# Server_UART_JTAG.net
KiCad netlist of a schematic drawn in Altium Designer
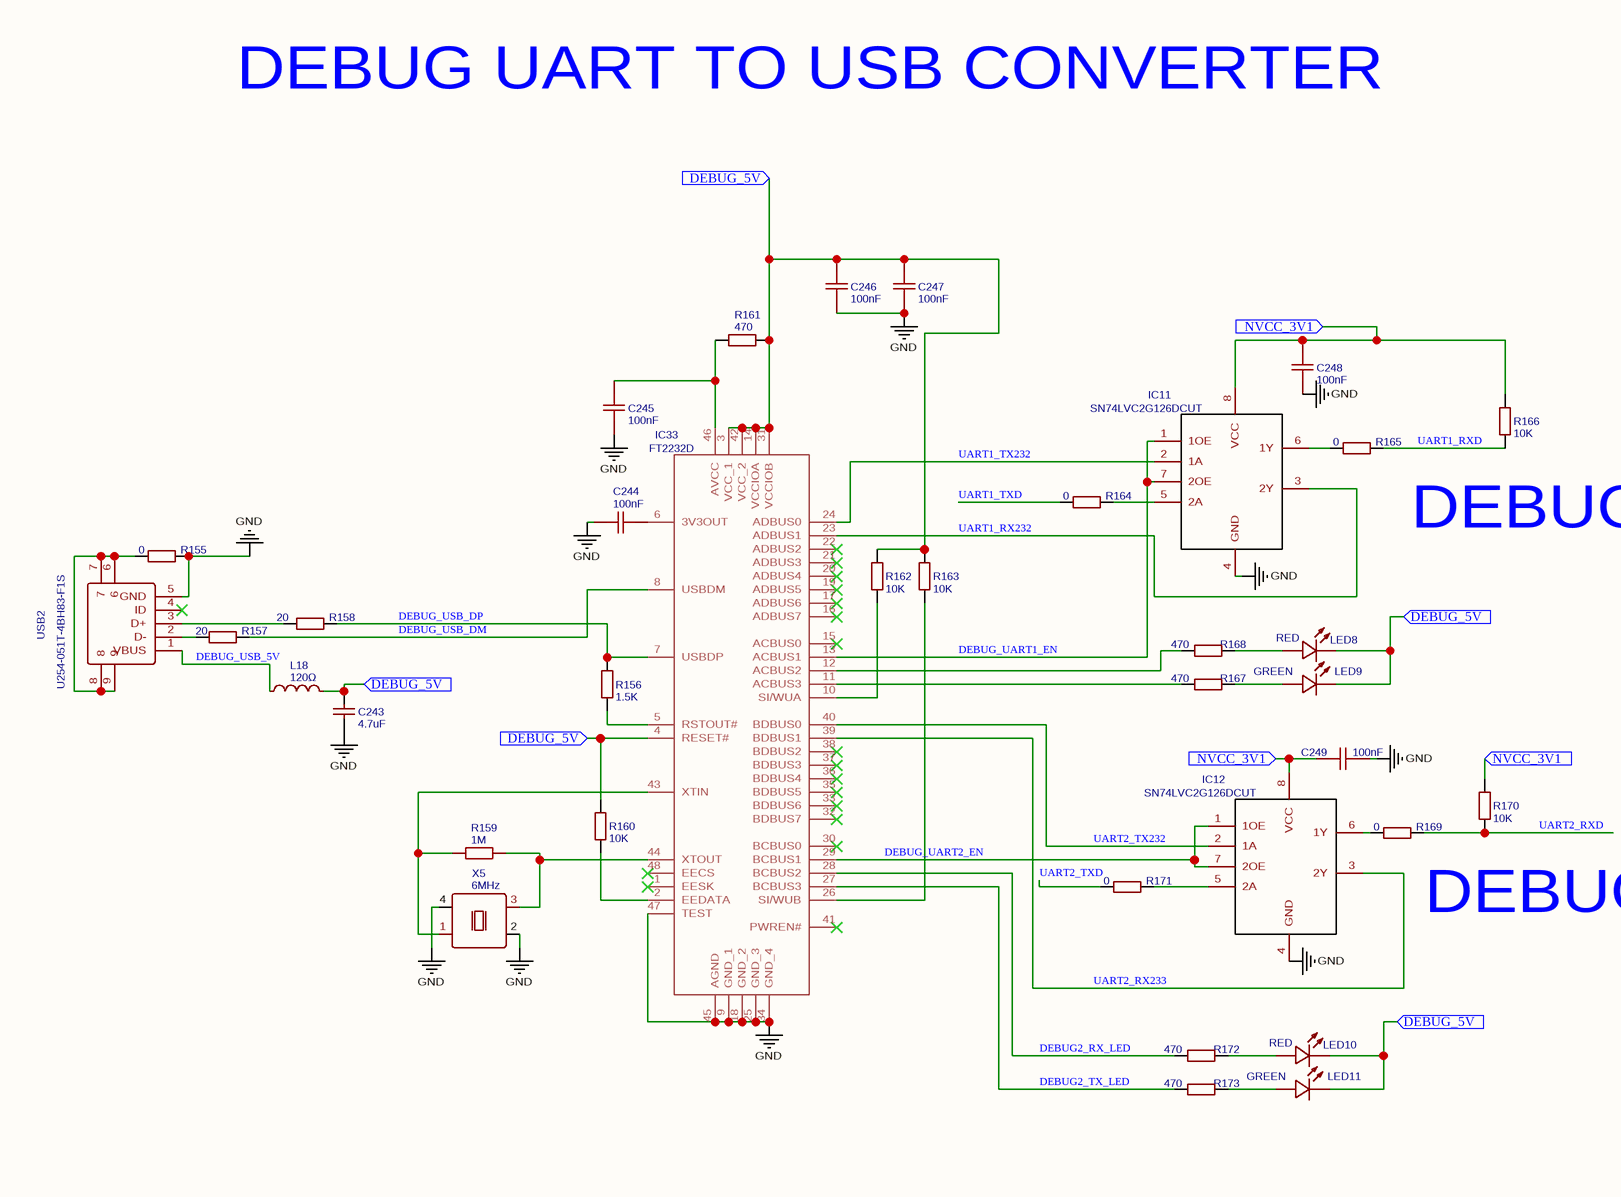
[diagram p0: Server UART & JTAG.schdoc, left]
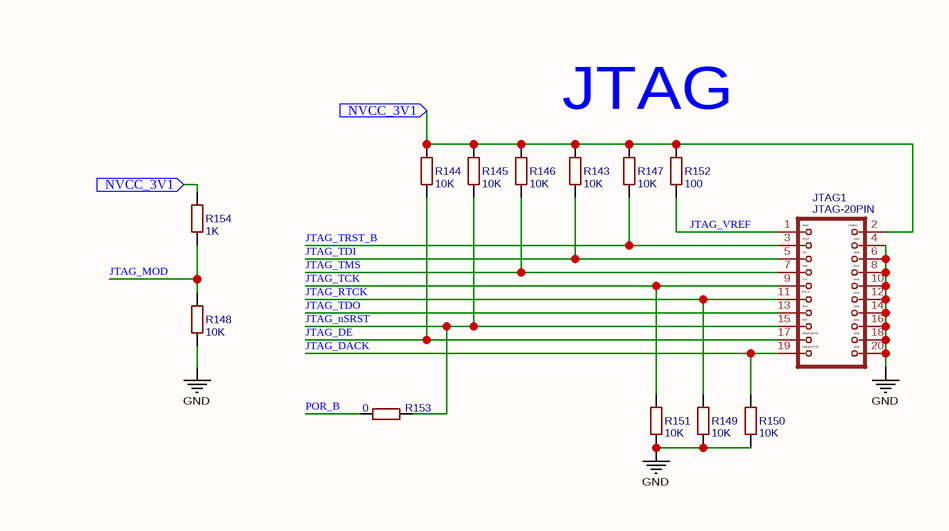
[diagram p1: Server UART & JTAG.schdoc, right]

(export (version "E")
  (design (tool "Eeschema 10.0.6"))
  (components
    (comp (ref "C243")
      (value "4.7uF")
      (fields
        (field (name "BOM_MANUFACTURER PART") "CL10A475KO8NNNC")
        (field (name "BOM_SUPPLIER PART") "C19666")
      )
      (libsource (lib "altium-import") (part "root_1_4.7uF_"))
    )
    (comp (ref "C244")
      (value "100nF")
      (fields
        (field (name "BOM_MANUFACTURER PART") "CC0603KRX7R9BB104")
        (field (name "BOM_SUPPLIER PART") "C14663")
      )
      (libsource (lib "altium-import") (part "root_2_100nF_"))
    )
    (comp (ref "C245")
      (value "100nF")
      (fields
        (field (name "BOM_MANUFACTURER PART") "CC0603KRX7R9BB104")
        (field (name "BOM_SUPPLIER PART") "C14663")
      )
      (libsource (lib "altium-import") (part "root_3_100nF_"))
    )
    (comp (ref "C246")
      (value "100nF")
      (fields
        (field (name "BOM_MANUFACTURER PART") "CC0603KRX7R9BB104")
        (field (name "BOM_SUPPLIER PART") "C14663")
      )
      (libsource (lib "altium-import") (part "root_3_100nF_"))
    )
    (comp (ref "C247")
      (value "100nF")
      (fields
        (field (name "BOM_MANUFACTURER PART") "CC0603KRX7R9BB104")
        (field (name "BOM_SUPPLIER PART") "C14663")
      )
      (libsource (lib "altium-import") (part "root_3_100nF_"))
    )
    (comp (ref "C248")
      (value "100nF")
      (fields
        (field (name "BOM_MANUFACTURER PART") "CC0603KRX7R9BB104")
        (field (name "BOM_SUPPLIER PART") "C14663")
      )
      (libsource (lib "altium-import") (part "root_3_100nF_"))
    )
    (comp (ref "C249")
      (value "100nF")
      (fields
        (field (name "BOM_MANUFACTURER PART") "CC0603KRX7R9BB104")
        (field (name "BOM_SUPPLIER PART") "C14663")
      )
      (libsource (lib "altium-import") (part "root_0_100nF_"))
    )
    (comp (ref "IC11")
      (value "SN74LVC2G126DCUT")
      (fields (field (name "CONTRIBUTOR") "Ke'Ondrae_Mell"))
      (libsource (lib "altium-import") (part "root_0_SN74LVC2G126DCUT_"))
    )
    (comp (ref "IC12")
      (value "SN74LVC2G126DCUT")
      (fields (field (name "CONTRIBUTOR") "Ke'Ondrae_Mell"))
      (libsource (lib "altium-import") (part "root_0_SN74LVC2G126DCUT_"))
    )
    (comp (ref "IC33")
      (value "FT2232D")
      (fields (field (name "CONTRIBUTOR") "Ke'Ondrae_Mell"))
      (libsource (lib "altium-import") (part "root_0_FT2232D_"))
    )
    (comp (ref "JTAG1")
      (value "JTAG-20PIN")
      (description "JTAG 20 Pin Programming Connector")
      (fields (field (name "CONTRIBUTOR") "PatternAgents"))
      (libsource (lib "altium-import") (part "root_0_JTAG-20PIN_"))
    )
    (comp (ref "L18")
      (value "120Ω")
      (fields
        (field (name "BOM_MANUFACTURER PART") "MMZ1005F121ET000")
        (field (name "BOM_SUPPLIER PART") "C89458")
      )
      (libsource (lib "altium-import") (part "root_0_120Ω_"))
    )
    (comp (ref "LED8")
      (value "RED")
      (fields
        (field (name "BOM_MANUFACTURER PART") "16-213UYOC/S530-A2/TR8")
        (field (name "BOM_SUPPLIER PART") "C88330")
      )
      (libsource (lib "altium-import") (part "root_0_RED_"))
    )
    (comp (ref "LED9")
      (value "GREEN")
      (fields
        (field (name "BOM_MANUFACTURER PART") "16-213UYOC/S530-A2/TR8")
        (field (name "BOM_SUPPLIER PART") "C88330")
      )
      (libsource (lib "altium-import") (part "root_0_GREEN_"))
    )
    (comp (ref "LED10")
      (value "RED")
      (fields
        (field (name "BOM_MANUFACTURER PART") "16-213UYOC/S530-A2/TR8")
        (field (name "BOM_SUPPLIER PART") "C88330")
      )
      (libsource (lib "altium-import") (part "root_0_RED_"))
    )
    (comp (ref "LED11")
      (value "GREEN")
      (fields
        (field (name "BOM_MANUFACTURER PART") "16-213UYOC/S530-A2/TR8")
        (field (name "BOM_SUPPLIER PART") "C88330")
      )
      (libsource (lib "altium-import") (part "root_0_GREEN_"))
    )
    (comp (ref "R143")
      (value "10K")
      (fields
        (field (name "BOM_MANUFACTURER PART") "0402WGF1002TCE")
        (field (name "BOM_SUPPLIER PART") "C25744")
      )
      (libsource (lib "altium-import") (part "root_1_10K_"))
    )
    (comp (ref "R144")
      (value "10K")
      (fields
        (field (name "BOM_MANUFACTURER PART") "0402WGF1002TCE")
        (field (name "BOM_SUPPLIER PART") "C25744")
      )
      (libsource (lib "altium-import") (part "root_1_10K_"))
    )
    (comp (ref "R145")
      (value "10K")
      (fields
        (field (name "BOM_MANUFACTURER PART") "0402WGF1002TCE")
        (field (name "BOM_SUPPLIER PART") "C25744")
      )
      (libsource (lib "altium-import") (part "root_1_10K_"))
    )
    (comp (ref "R146")
      (value "10K")
      (fields
        (field (name "BOM_MANUFACTURER PART") "0402WGF1002TCE")
        (field (name "BOM_SUPPLIER PART") "C25744")
      )
      (libsource (lib "altium-import") (part "root_1_10K_"))
    )
    (comp (ref "R147")
      (value "10K")
      (fields
        (field (name "BOM_MANUFACTURER PART") "0402WGF1002TCE")
        (field (name "BOM_SUPPLIER PART") "C25744")
      )
      (libsource (lib "altium-import") (part "root_1_10K_"))
    )
    (comp (ref "R148")
      (value "10K")
      (fields
        (field (name "BOM_MANUFACTURER PART") "0402WGF1002TCE")
        (field (name "BOM_SUPPLIER PART") "C25744")
      )
      (libsource (lib "altium-import") (part "root_1_10K_"))
    )
    (comp (ref "R149")
      (value "10K")
      (fields
        (field (name "BOM_MANUFACTURER PART") "0402WGF1002TCE")
        (field (name "BOM_SUPPLIER PART") "C25744")
      )
      (libsource (lib "altium-import") (part "root_1_10K_"))
    )
    (comp (ref "R150")
      (value "10K")
      (fields
        (field (name "BOM_MANUFACTURER PART") "0402WGF1002TCE")
        (field (name "BOM_SUPPLIER PART") "C25744")
      )
      (libsource (lib "altium-import") (part "root_1_10K_"))
    )
    (comp (ref "R151")
      (value "10K")
      (fields
        (field (name "BOM_MANUFACTURER PART") "0402WGF1002TCE")
        (field (name "BOM_SUPPLIER PART") "C25744")
      )
      (libsource (lib "altium-import") (part "root_1_10K_"))
    )
    (comp (ref "R152")
      (value "100")
      (fields
        (field (name "BOM_MANUFACTURER PART") "TC0225F1000TCE")
        (field (name "BOM_SUPPLIER PART") "C98836")
      )
      (libsource (lib "altium-import") (part "root_1_100_"))
    )
    (comp (ref "R153")
      (value "0")
      (fields
        (field (name "BOM_MANUFACTURER PART") "RK73Z1ETTP")
        (field (name "BOM_SUPPLIER PART") "C131359")
      )
      (libsource (lib "altium-import") (part "root_0_0_"))
    )
    (comp (ref "R154")
      (value "1K")
      (fields
        (field (name "BOM_MANUFACTURER PART") "TC0225F1001TCE")
        (field (name "BOM_SUPPLIER PART") "C98841")
      )
      (libsource (lib "altium-import") (part "root_1_1K_"))
    )
    (comp (ref "R155")
      (value "0")
      (fields
        (field (name "BOM_MANUFACTURER PART") "RK73Z1ETTP")
        (field (name "BOM_SUPPLIER PART") "C131359")
      )
      (libsource (lib "altium-import") (part "root_0_0_"))
    )
    (comp (ref "R156")
      (value "1.5K")
      (fields
        (field (name "BOM_MANUFACTURER PART") "0402WGF1501TCE")
        (field (name "BOM_SUPPLIER PART") "C25867")
      )
      (libsource (lib "altium-import") (part "root_1_1.5K_"))
    )
    (comp (ref "R157")
      (value "20")
      (fields
        (field (name "BOM_MANUFACTURER PART") "0805W8F200JT5E")
        (field (name "BOM_SUPPLIER PART") "C17544")
      )
      (libsource (lib "altium-import") (part "root_0_20_"))
    )
    (comp (ref "R158")
      (value "20")
      (fields
        (field (name "BOM_MANUFACTURER PART") "0805W8F200JT5E")
        (field (name "BOM_SUPPLIER PART") "C17544")
      )
      (libsource (lib "altium-import") (part "root_0_20_"))
    )
    (comp (ref "R159")
      (value "1M")
      (fields
        (field (name "BOM_SUPPLIER PART") "C269705")
        (field (name "BOM_MANUFACTURER PART") "RMC06031M1%N")
        (field (name "CONTRIBUTOR") "LCSC")
      )
      (libsource (lib "altium-import") (part "root_0_1M_"))
    )
    (comp (ref "R160")
      (value "10K")
      (fields
        (field (name "BOM_MANUFACTURER PART") "0402WGF1002TCE")
        (field (name "BOM_SUPPLIER PART") "C25744")
      )
      (libsource (lib "altium-import") (part "root_1_10K_"))
    )
    (comp (ref "R161")
      (value "470")
      (fields
        (field (name "BOM_MANUFACTURER PART") "0402WGF4700TCE")
        (field (name "BOM_SUPPLIER PART") "C25117")
      )
      (libsource (lib "altium-import") (part "root_0_470_"))
    )
    (comp (ref "R162")
      (value "10K")
      (fields
        (field (name "BOM_MANUFACTURER PART") "0402WGF1002TCE")
        (field (name "BOM_SUPPLIER PART") "C25744")
      )
      (libsource (lib "altium-import") (part "root_1_10K_"))
    )
    (comp (ref "R163")
      (value "10K")
      (fields
        (field (name "BOM_MANUFACTURER PART") "0402WGF1002TCE")
        (field (name "BOM_SUPPLIER PART") "C25744")
      )
      (libsource (lib "altium-import") (part "root_1_10K_"))
    )
    (comp (ref "R164")
      (value "0")
      (fields
        (field (name "BOM_MANUFACTURER PART") "RK73Z1ETTP")
        (field (name "BOM_SUPPLIER PART") "C131359")
      )
      (libsource (lib "altium-import") (part "root_0_0_"))
    )
    (comp (ref "R165")
      (value "0")
      (fields
        (field (name "BOM_MANUFACTURER PART") "RK73Z1ETTP")
        (field (name "BOM_SUPPLIER PART") "C131359")
      )
      (libsource (lib "altium-import") (part "root_0_0_"))
    )
    (comp (ref "R166")
      (value "10K")
      (fields
        (field (name "BOM_MANUFACTURER PART") "0402WGF1002TCE")
        (field (name "BOM_SUPPLIER PART") "C25744")
      )
      (libsource (lib "altium-import") (part "root_1_10K_"))
    )
    (comp (ref "R167")
      (value "470")
      (fields
        (field (name "BOM_MANUFACTURER PART") "0402WGF4700TCE")
        (field (name "BOM_SUPPLIER PART") "C25117")
      )
      (libsource (lib "altium-import") (part "root_0_470_"))
    )
    (comp (ref "R168")
      (value "470")
      (fields
        (field (name "BOM_MANUFACTURER PART") "0402WGF4700TCE")
        (field (name "BOM_SUPPLIER PART") "C25117")
      )
      (libsource (lib "altium-import") (part "root_0_470_"))
    )
    (comp (ref "R169")
      (value "0")
      (fields
        (field (name "BOM_MANUFACTURER PART") "RK73Z1ETTP")
        (field (name "BOM_SUPPLIER PART") "C131359")
      )
      (libsource (lib "altium-import") (part "root_0_0_"))
    )
    (comp (ref "R170")
      (value "10K")
      (fields
        (field (name "BOM_MANUFACTURER PART") "0402WGF1002TCE")
        (field (name "BOM_SUPPLIER PART") "C25744")
      )
      (libsource (lib "altium-import") (part "root_1_10K_"))
    )
    (comp (ref "R171")
      (value "0")
      (fields
        (field (name "BOM_MANUFACTURER PART") "RK73Z1ETTP")
        (field (name "BOM_SUPPLIER PART") "C131359")
      )
      (libsource (lib "altium-import") (part "root_0_0_"))
    )
    (comp (ref "R172")
      (value "470")
      (fields
        (field (name "BOM_MANUFACTURER PART") "0402WGF4700TCE")
        (field (name "BOM_SUPPLIER PART") "C25117")
      )
      (libsource (lib "altium-import") (part "root_0_470_"))
    )
    (comp (ref "R173")
      (value "470")
      (fields
        (field (name "BOM_MANUFACTURER PART") "0402WGF4700TCE")
        (field (name "BOM_SUPPLIER PART") "C25117")
      )
      (libsource (lib "altium-import") (part "root_0_470_"))
    )
    (comp (ref "USB2")
      (value "U254-051T-4BH83-F1S")
      (fields (field (name "BOM_SUPPLIER PART") "C397452") (field (name "CONTRIBUTOR") "LCSC"))
      (libsource (lib "altium-import") (part "root_2_U254-051T-4BH83-F1S_"))
    )
    (comp (ref "X5")
      (value "6MHz")
      (fields
        (field (name "BOM_SUPPLIER PART") "C295516")
        (field (name "BOM_MANUFACTURER PART") "OVETGLJANF-6MHZ")
        (field (name "CONTRIBUTOR") "LCSC")
      )
      (libsource (lib "altium-import") (part "root_0_6MHz_"))
    )
  )
  (nets
    (net (code "1") (name "/DEBUG2_RX_LED") (class "Default")
      (node (ref "IC33") (pin "28") (pinfunction "BCBUS2_28") (pintype "passive"))
      (node (ref "R172") (pin "1") (pinfunction "1_1") (pintype "passive"))
    )
    (net (code "2") (name "/DEBUG2_TX_LED") (class "Default")
      (node (ref "IC33") (pin "27") (pinfunction "BCBUS3_27") (pintype "passive"))
      (node (ref "R173") (pin "1") (pinfunction "1_1") (pintype "passive"))
    )
    (net (code "3") (name "/DEBUG_5V") (class "Default")
      (node (ref "C243") (pin "2") (pinfunction "2_2") (pintype "passive"))
      (node (ref "C246") (pin "1") (pinfunction "1_1") (pintype "passive"))
      (node (ref "C247") (pin "1") (pinfunction "1_1") (pintype "passive"))
      (node (ref "IC33") (pin "14") (pinfunction "VCCIOA_14") (pintype "passive"))
      (node (ref "IC33") (pin "3") (pinfunction "VCC_1_3") (pintype "passive"))
      (node (ref "IC33") (pin "31") (pinfunction "VCCIOB_31") (pintype "passive"))
      (node (ref "IC33") (pin "4") (pinfunction "RESET#_4") (pintype "passive"))
      (node (ref "IC33") (pin "42") (pinfunction "VCC_2_42") (pintype "passive"))
      (node (ref "L18") (pin "2") (pinfunction "2_2") (pintype "passive"))
      (node (ref "LED10") (pin "2") (pinfunction "K_2") (pintype "passive"))
      (node (ref "LED11") (pin "2") (pinfunction "K_2") (pintype "passive"))
      (node (ref "LED8") (pin "2") (pinfunction "K_2") (pintype "passive"))
      (node (ref "LED9") (pin "2") (pinfunction "K_2") (pintype "passive"))
      (node (ref "R160") (pin "2") (pinfunction "2_2") (pintype "passive"))
      (node (ref "R161") (pin "2") (pinfunction "2_2") (pintype "passive"))
      (node (ref "R162") (pin "2") (pinfunction "2_2") (pintype "passive"))
      (node (ref "R163") (pin "2") (pinfunction "2_2") (pintype "passive"))
    )
    (net (code "4") (name "/DEBUG_UART1_EN") (class "Default")
      (node (ref "IC11") (pin "1") (pinfunction "1OE_1") (pintype "passive"))
      (node (ref "IC11") (pin "7") (pinfunction "2OE_7") (pintype "passive"))
      (node (ref "IC33") (pin "13") (pinfunction "ACBUS1_13") (pintype "passive"))
    )
    (net (code "5") (name "/DEBUG_UART2_EN") (class "Default")
      (node (ref "IC12") (pin "1") (pinfunction "1OE_1") (pintype "passive"))
      (node (ref "IC12") (pin "7") (pinfunction "2OE_7") (pintype "passive"))
      (node (ref "IC33") (pin "29") (pinfunction "BCBUS1_29") (pintype "passive"))
    )
    (net (code "6") (name "/DEBUG_USB_5V") (class "Default")
      (node (ref "L18") (pin "1") (pinfunction "1_1") (pintype "passive"))
      (node (ref "USB2") (pin "1") (pinfunction "VBUS_1") (pintype "passive"))
    )
    (net (code "7") (name "/DEBUG_USB_DM") (class "Default")
      (node (ref "IC33") (pin "8") (pinfunction "USBDM_8") (pintype "passive"))
      (node (ref "R157") (pin "2") (pinfunction "2_2") (pintype "passive"))
    )
    (net (code "8") (name "/DEBUG_USB_DP") (class "Default")
      (node (ref "IC33") (pin "7") (pinfunction "USBDP_7") (pintype "passive"))
      (node (ref "R156") (pin "2") (pinfunction "2_2") (pintype "passive"))
      (node (ref "R158") (pin "2") (pinfunction "2_2") (pintype "passive"))
    )
    (net (code "9") (name "/JTAG_DACK") (class "Default")
      (node (ref "JTAG1") (pin "19") (pinfunction "19_19") (pintype "passive"))
      (node (ref "R150") (pin "2") (pinfunction "2_2") (pintype "passive"))
    )
    (net (code "10") (name "/JTAG_DE") (class "Default")
      (node (ref "JTAG1") (pin "17") (pinfunction "17_17") (pintype "passive"))
      (node (ref "R144") (pin "1") (pinfunction "1_1") (pintype "passive"))
    )
    (net (code "11") (name "/JTAG_MOD") (class "Default")
      (node (ref "R148") (pin "2") (pinfunction "2_2") (pintype "passive"))
      (node (ref "R154") (pin "1") (pinfunction "1_1") (pintype "passive"))
    )
    (net (code "12") (name "/JTAG_RTCK") (class "Default")
      (node (ref "JTAG1") (pin "11") (pinfunction "11_11") (pintype "passive"))
      (node (ref "R149") (pin "2") (pinfunction "2_2") (pintype "passive"))
    )
    (net (code "13") (name "/JTAG_TCK") (class "Default")
      (node (ref "JTAG1") (pin "9") (pinfunction "9_9") (pintype "passive"))
      (node (ref "R151") (pin "2") (pinfunction "2_2") (pintype "passive"))
    )
    (net (code "14") (name "/JTAG_TDI") (class "Default")
      (node (ref "JTAG1") (pin "5") (pinfunction "5_5") (pintype "passive"))
      (node (ref "R143") (pin "1") (pinfunction "1_1") (pintype "passive"))
    )
    (net (code "15") (name "/JTAG_TDO") (class "Default")
      (node (ref "JTAG1") (pin "13") (pinfunction "13_13") (pintype "passive"))
    )
    (net (code "16") (name "/JTAG_TMS") (class "Default")
      (node (ref "JTAG1") (pin "7") (pinfunction "7_7") (pintype "passive"))
      (node (ref "R146") (pin "1") (pinfunction "1_1") (pintype "passive"))
    )
    (net (code "17") (name "/JTAG_TRST_B") (class "Default")
      (node (ref "JTAG1") (pin "3") (pinfunction "3_3") (pintype "passive"))
      (node (ref "R147") (pin "1") (pinfunction "1_1") (pintype "passive"))
    )
    (net (code "18") (name "/JTAG_VREF") (class "Default")
      (node (ref "JTAG1") (pin "1") (pinfunction "1_1") (pintype "passive"))
      (node (ref "R152") (pin "1") (pinfunction "1_1") (pintype "passive"))
    )
    (net (code "19") (name "/JTAG_nSRST") (class "Default")
      (node (ref "JTAG1") (pin "15") (pinfunction "15_15") (pintype "passive"))
      (node (ref "R145") (pin "1") (pinfunction "1_1") (pintype "passive"))
      (node (ref "R153") (pin "2") (pinfunction "2_2") (pintype "passive"))
    )
    (net (code "20") (name "/NVCC_3V1") (class "Default")
      (node (ref "C248") (pin "1") (pinfunction "1_1") (pintype "passive"))
      (node (ref "C249") (pin "1") (pinfunction "1_1") (pintype "passive"))
      (node (ref "IC11") (pin "8") (pinfunction "VCC_8") (pintype "passive"))
      (node (ref "IC12") (pin "8") (pinfunction "VCC_8") (pintype "passive"))
      (node (ref "JTAG1") (pin "2") (pinfunction "2_2") (pintype "passive"))
      (node (ref "R143") (pin "2") (pinfunction "2_2") (pintype "passive"))
      (node (ref "R144") (pin "2") (pinfunction "2_2") (pintype "passive"))
      (node (ref "R145") (pin "2") (pinfunction "2_2") (pintype "passive"))
      (node (ref "R146") (pin "2") (pinfunction "2_2") (pintype "passive"))
      (node (ref "R147") (pin "2") (pinfunction "2_2") (pintype "passive"))
      (node (ref "R152") (pin "2") (pinfunction "2_2") (pintype "passive"))
      (node (ref "R154") (pin "2") (pinfunction "2_2") (pintype "passive"))
      (node (ref "R166") (pin "2") (pinfunction "2_2") (pintype "passive"))
      (node (ref "R170") (pin "2") (pinfunction "2_2") (pintype "passive"))
    )
    (net (code "21") (name "/POR_B") (class "Default")
      (node (ref "R153") (pin "1") (pinfunction "1_1") (pintype "passive"))
    )
    (net (code "22") (name "/UART1_RX232") (class "Default")
      (node (ref "IC11") (pin "3") (pinfunction "2Y_3") (pintype "passive"))
      (node (ref "IC33") (pin "23") (pinfunction "ADBUS1_23") (pintype "passive"))
    )
    (net (code "23") (name "/UART1_RXD") (class "Default")
      (node (ref "R165") (pin "2") (pinfunction "2_2") (pintype "passive"))
      (node (ref "R166") (pin "1") (pinfunction "1_1") (pintype "passive"))
    )
    (net (code "24") (name "/UART1_TX232") (class "Default")
      (node (ref "IC11") (pin "2") (pinfunction "1A_2") (pintype "passive"))
      (node (ref "IC33") (pin "24") (pinfunction "ADBUS0_24") (pintype "passive"))
    )
    (net (code "25") (name "/UART1_TXD") (class "Default")
      (node (ref "R164") (pin "1") (pinfunction "1_1") (pintype "passive"))
    )
    (net (code "26") (name "/UART2_RX233") (class "Default")
      (node (ref "IC12") (pin "3") (pinfunction "2Y_3") (pintype "passive"))
      (node (ref "IC33") (pin "39") (pinfunction "BDBUS1_39") (pintype "passive"))
    )
    (net (code "27") (name "/UART2_RXD") (class "Default")
      (node (ref "R169") (pin "2") (pinfunction "2_2") (pintype "passive"))
      (node (ref "R170") (pin "1") (pinfunction "1_1") (pintype "passive"))
    )
    (net (code "28") (name "/UART2_TX232") (class "Default")
      (node (ref "IC12") (pin "2") (pinfunction "1A_2") (pintype "passive"))
      (node (ref "IC33") (pin "40") (pinfunction "BDBUS0_40") (pintype "passive"))
    )
    (net (code "29") (name "/UART2_TXD") (class "Default")
      (node (ref "R171") (pin "1") (pinfunction "1_1") (pintype "passive"))
    )
    (net (code "30") (name "GND") (class "Default")
      (node (ref "C243") (pin "1") (pinfunction "1_1") (pintype "passive"))
      (node (ref "C244") (pin "2") (pinfunction "2_2") (pintype "passive"))
      (node (ref "C245") (pin "2") (pinfunction "2_2") (pintype "passive"))
      (node (ref "C246") (pin "2") (pinfunction "2_2") (pintype "passive"))
      (node (ref "C247") (pin "2") (pinfunction "2_2") (pintype "passive"))
      (node (ref "C248") (pin "2") (pinfunction "2_2") (pintype "passive"))
      (node (ref "C249") (pin "2") (pinfunction "2_2") (pintype "passive"))
      (node (ref "IC11") (pin "4") (pinfunction "GND_4") (pintype "passive"))
      (node (ref "IC12") (pin "4") (pinfunction "GND_4") (pintype "passive"))
      (node (ref "IC33") (pin "18") (pinfunction "GND_2_18") (pintype "passive"))
      (node (ref "IC33") (pin "25") (pinfunction "GND_3_25") (pintype "passive"))
      (node (ref "IC33") (pin "34") (pinfunction "GND_4_34") (pintype "passive"))
      (node (ref "IC33") (pin "45") (pinfunction "AGND_45") (pintype "passive"))
      (node (ref "IC33") (pin "47") (pinfunction "TEST_47") (pintype "passive"))
      (node (ref "IC33") (pin "9") (pinfunction "GND_1_9") (pintype "passive"))
      (node (ref "JTAG1") (pin "10") (pinfunction "10_10") (pintype "passive"))
      (node (ref "JTAG1") (pin "12") (pinfunction "12_12") (pintype "passive"))
      (node (ref "JTAG1") (pin "14") (pinfunction "14_14") (pintype "passive"))
      (node (ref "JTAG1") (pin "16") (pinfunction "16_16") (pintype "passive"))
      (node (ref "JTAG1") (pin "18") (pinfunction "18_18") (pintype "passive"))
      (node (ref "JTAG1") (pin "20") (pinfunction "20_20") (pintype "passive"))
      (node (ref "JTAG1") (pin "4") (pinfunction "4_4") (pintype "passive"))
      (node (ref "JTAG1") (pin "6") (pinfunction "6_6") (pintype "passive"))
      (node (ref "JTAG1") (pin "8") (pinfunction "8_8") (pintype "passive"))
      (node (ref "R148") (pin "1") (pinfunction "1_1") (pintype "passive"))
      (node (ref "R149") (pin "1") (pinfunction "1_1") (pintype "passive"))
      (node (ref "R150") (pin "1") (pinfunction "1_1") (pintype "passive"))
      (node (ref "R151") (pin "1") (pinfunction "1_1") (pintype "passive"))
      (node (ref "R155") (pin "2") (pinfunction "2_2") (pintype "passive"))
      (node (ref "USB2") (pin "5") (pinfunction "GND_5") (pintype "passive"))
      (node (ref "X5") (pin "2") (pinfunction "GND_2") (pintype "passive"))
      (node (ref "X5") (pin "4") (pinfunction "VCC_4") (pintype "passive"))
    )
    (net (code "31") (name "Net-(IC11-1Y)") (class "Default")
      (node (ref "IC11") (pin "6") (pinfunction "1Y_6") (pintype "passive"))
      (node (ref "R165") (pin "1") (pinfunction "1_1") (pintype "passive"))
    )
    (net (code "32") (name "Net-(IC11-2A)") (class "Default")
      (node (ref "IC11") (pin "5") (pinfunction "2A_5") (pintype "passive"))
      (node (ref "R164") (pin "2") (pinfunction "2_2") (pintype "passive"))
    )
    (net (code "33") (name "Net-(IC12-1Y)") (class "Default")
      (node (ref "IC12") (pin "6") (pinfunction "1Y_6") (pintype "passive"))
      (node (ref "R169") (pin "1") (pinfunction "1_1") (pintype "passive"))
    )
    (net (code "34") (name "Net-(IC12-2A)") (class "Default")
      (node (ref "IC12") (pin "5") (pinfunction "2A_5") (pintype "passive"))
      (node (ref "R171") (pin "2") (pinfunction "2_2") (pintype "passive"))
    )
    (net (code "35") (name "Net-(IC33-3V3OUT)") (class "Default")
      (node (ref "C244") (pin "1") (pinfunction "1_1") (pintype "passive"))
      (node (ref "IC33") (pin "6") (pinfunction "3V3OUT_6") (pintype "passive"))
    )
    (net (code "36") (name "Net-(IC33-ACBUS2)") (class "Default")
      (node (ref "IC33") (pin "12") (pinfunction "ACBUS2_12") (pintype "passive"))
      (node (ref "R168") (pin "1") (pinfunction "1_1") (pintype "passive"))
    )
    (net (code "37") (name "Net-(IC33-ACBUS3)") (class "Default")
      (node (ref "IC33") (pin "11") (pinfunction "ACBUS3_11") (pintype "passive"))
      (node (ref "R167") (pin "1") (pinfunction "1_1") (pintype "passive"))
    )
    (net (code "38") (name "Net-(IC33-AVCC)") (class "Default")
      (node (ref "C245") (pin "1") (pinfunction "1_1") (pintype "passive"))
      (node (ref "IC33") (pin "46") (pinfunction "AVCC_46") (pintype "passive"))
      (node (ref "R161") (pin "1") (pinfunction "1_1") (pintype "passive"))
    )
    (net (code "39") (name "Net-(IC33-EEDATA)") (class "Default")
      (node (ref "IC33") (pin "2") (pinfunction "EEDATA_2") (pintype "passive"))
      (node (ref "R160") (pin "1") (pinfunction "1_1") (pintype "passive"))
    )
    (net (code "40") (name "Net-(IC33-RSTOUT#)") (class "Default")
      (node (ref "IC33") (pin "5") (pinfunction "RSTOUT#_5") (pintype "passive"))
      (node (ref "R156") (pin "1") (pinfunction "1_1") (pintype "passive"))
    )
    (net (code "41") (name "Net-(IC33-SI{slash}WUA)") (class "Default")
      (node (ref "IC33") (pin "10") (pinfunction "SI/WUA_10") (pintype "passive"))
      (node (ref "R162") (pin "1") (pinfunction "1_1") (pintype "passive"))
    )
    (net (code "42") (name "Net-(IC33-SI{slash}WUB)") (class "Default")
      (node (ref "IC33") (pin "26") (pinfunction "SI/WUB_26") (pintype "passive"))
      (node (ref "R163") (pin "1") (pinfunction "1_1") (pintype "passive"))
    )
    (net (code "43") (name "Net-(IC33-XTIN)") (class "Default")
      (node (ref "IC33") (pin "43") (pinfunction "XTIN_43") (pintype "passive"))
      (node (ref "R159") (pin "1") (pinfunction "1_1") (pintype "passive"))
      (node (ref "X5") (pin "1") (pinfunction "tri_1") (pintype "passive"))
    )
    (net (code "44") (name "Net-(IC33-XTOUT)") (class "Default")
      (node (ref "IC33") (pin "44") (pinfunction "XTOUT_44") (pintype "passive"))
      (node (ref "R159") (pin "2") (pinfunction "2_2") (pintype "passive"))
      (node (ref "X5") (pin "3") (pinfunction "OUT_3") (pintype "passive"))
    )
    (net (code "45") (name "Net-(LED8-A)") (class "Default")
      (node (ref "LED8") (pin "1") (pinfunction "A_1") (pintype "passive"))
      (node (ref "R168") (pin "2") (pinfunction "2_2") (pintype "passive"))
    )
    (net (code "46") (name "Net-(LED9-A)") (class "Default")
      (node (ref "LED9") (pin "1") (pinfunction "A_1") (pintype "passive"))
      (node (ref "R167") (pin "2") (pinfunction "2_2") (pintype "passive"))
    )
    (net (code "47") (name "Net-(LED10-A)") (class "Default")
      (node (ref "LED10") (pin "1") (pinfunction "A_1") (pintype "passive"))
      (node (ref "R172") (pin "2") (pinfunction "2_2") (pintype "passive"))
    )
    (net (code "48") (name "Net-(LED11-A)") (class "Default")
      (node (ref "LED11") (pin "1") (pinfunction "A_1") (pintype "passive"))
      (node (ref "R173") (pin "2") (pinfunction "2_2") (pintype "passive"))
    )
    (net (code "49") (name "Net-(R155-Pad1)") (class "Default")
      (node (ref "R155") (pin "1") (pinfunction "1_1") (pintype "passive"))
      (node (ref "USB2") (pin "6") (pinfunction "6_6") (pintype "passive"))
      (node (ref "USB2") (pin "7") (pinfunction "7_7") (pintype "passive"))
      (node (ref "USB2") (pin "8") (pinfunction "8_8") (pintype "passive"))
      (node (ref "USB2") (pin "9") (pinfunction "9_9") (pintype "passive"))
    )
    (net (code "50") (name "Net-(USB2-D+)") (class "Default")
      (node (ref "R158") (pin "1") (pinfunction "1_1") (pintype "passive"))
      (node (ref "USB2") (pin "3") (pinfunction "D+_3") (pintype "passive"))
    )
    (net (code "51") (name "Net-(USB2-D-)") (class "Default")
      (node (ref "R157") (pin "1") (pinfunction "1_1") (pintype "passive"))
      (node (ref "USB2") (pin "2") (pinfunction "D-_2") (pintype "passive"))
    )
    (net (code "52") (name "unconnected-(IC33-ACBUS0-Pad15)") (class "Default")
      (node (ref "IC33") (pin "15") (pinfunction "ACBUS0_15") (pintype "passive+no_connect"))
    )
    (net (code "53") (name "unconnected-(IC33-ADBUS2-Pad22)") (class "Default")
      (node (ref "IC33") (pin "22") (pinfunction "ADBUS2_22") (pintype "passive+no_connect"))
    )
    (net (code "54") (name "unconnected-(IC33-ADBUS3-Pad21)") (class "Default")
      (node (ref "IC33") (pin "21") (pinfunction "ADBUS3_21") (pintype "passive+no_connect"))
    )
    (net (code "55") (name "unconnected-(IC33-ADBUS4-Pad20)") (class "Default")
      (node (ref "IC33") (pin "20") (pinfunction "ADBUS4_20") (pintype "passive+no_connect"))
    )
    (net (code "56") (name "unconnected-(IC33-ADBUS5-Pad19)") (class "Default")
      (node (ref "IC33") (pin "19") (pinfunction "ADBUS5_19") (pintype "passive+no_connect"))
    )
    (net (code "57") (name "unconnected-(IC33-ADBUS6-Pad17)") (class "Default")
      (node (ref "IC33") (pin "17") (pinfunction "ADBUS6_17") (pintype "passive+no_connect"))
    )
    (net (code "58") (name "unconnected-(IC33-ADBUS7-Pad16)") (class "Default")
      (node (ref "IC33") (pin "16") (pinfunction "ADBUS7_16") (pintype "passive+no_connect"))
    )
    (net (code "59") (name "unconnected-(IC33-BCBUS0-Pad30)") (class "Default")
      (node (ref "IC33") (pin "30") (pinfunction "BCBUS0_30") (pintype "passive+no_connect"))
    )
    (net (code "60") (name "unconnected-(IC33-BDBUS2-Pad38)") (class "Default")
      (node (ref "IC33") (pin "38") (pinfunction "BDBUS2_38") (pintype "passive+no_connect"))
    )
    (net (code "61") (name "unconnected-(IC33-BDBUS3-Pad37)") (class "Default")
      (node (ref "IC33") (pin "37") (pinfunction "BDBUS3_37") (pintype "passive+no_connect"))
    )
    (net (code "62") (name "unconnected-(IC33-BDBUS4-Pad36)") (class "Default")
      (node (ref "IC33") (pin "36") (pinfunction "BDBUS4_36") (pintype "passive+no_connect"))
    )
    (net (code "63") (name "unconnected-(IC33-BDBUS5-Pad35)") (class "Default")
      (node (ref "IC33") (pin "35") (pinfunction "BDBUS5_35") (pintype "passive+no_connect"))
    )
    (net (code "64") (name "unconnected-(IC33-BDBUS6-Pad33)") (class "Default")
      (node (ref "IC33") (pin "33") (pinfunction "BDBUS6_33") (pintype "passive+no_connect"))
    )
    (net (code "65") (name "unconnected-(IC33-BDBUS7-Pad32)") (class "Default")
      (node (ref "IC33") (pin "32") (pinfunction "BDBUS7_32") (pintype "passive+no_connect"))
    )
    (net (code "66") (name "unconnected-(IC33-EECS-Pad48)") (class "Default")
      (node (ref "IC33") (pin "48") (pinfunction "EECS_48") (pintype "passive+no_connect"))
    )
    (net (code "67") (name "unconnected-(IC33-EESK-Pad1)") (class "Default")
      (node (ref "IC33") (pin "1") (pinfunction "EESK_1") (pintype "passive+no_connect"))
    )
    (net (code "68") (name "unconnected-(IC33-PWREN#-Pad41)") (class "Default")
      (node (ref "IC33") (pin "41") (pinfunction "PWREN#_41") (pintype "passive+no_connect"))
    )
    (net (code "69") (name "unconnected-(USB2-ID-Pad4)") (class "Default")
      (node (ref "USB2") (pin "4") (pinfunction "ID_4") (pintype "passive+no_connect"))
    )
  )
)
